# k26_baseboard_usb_c_conn.net
KiCad netlist of a schematic drawn in Altium Designer
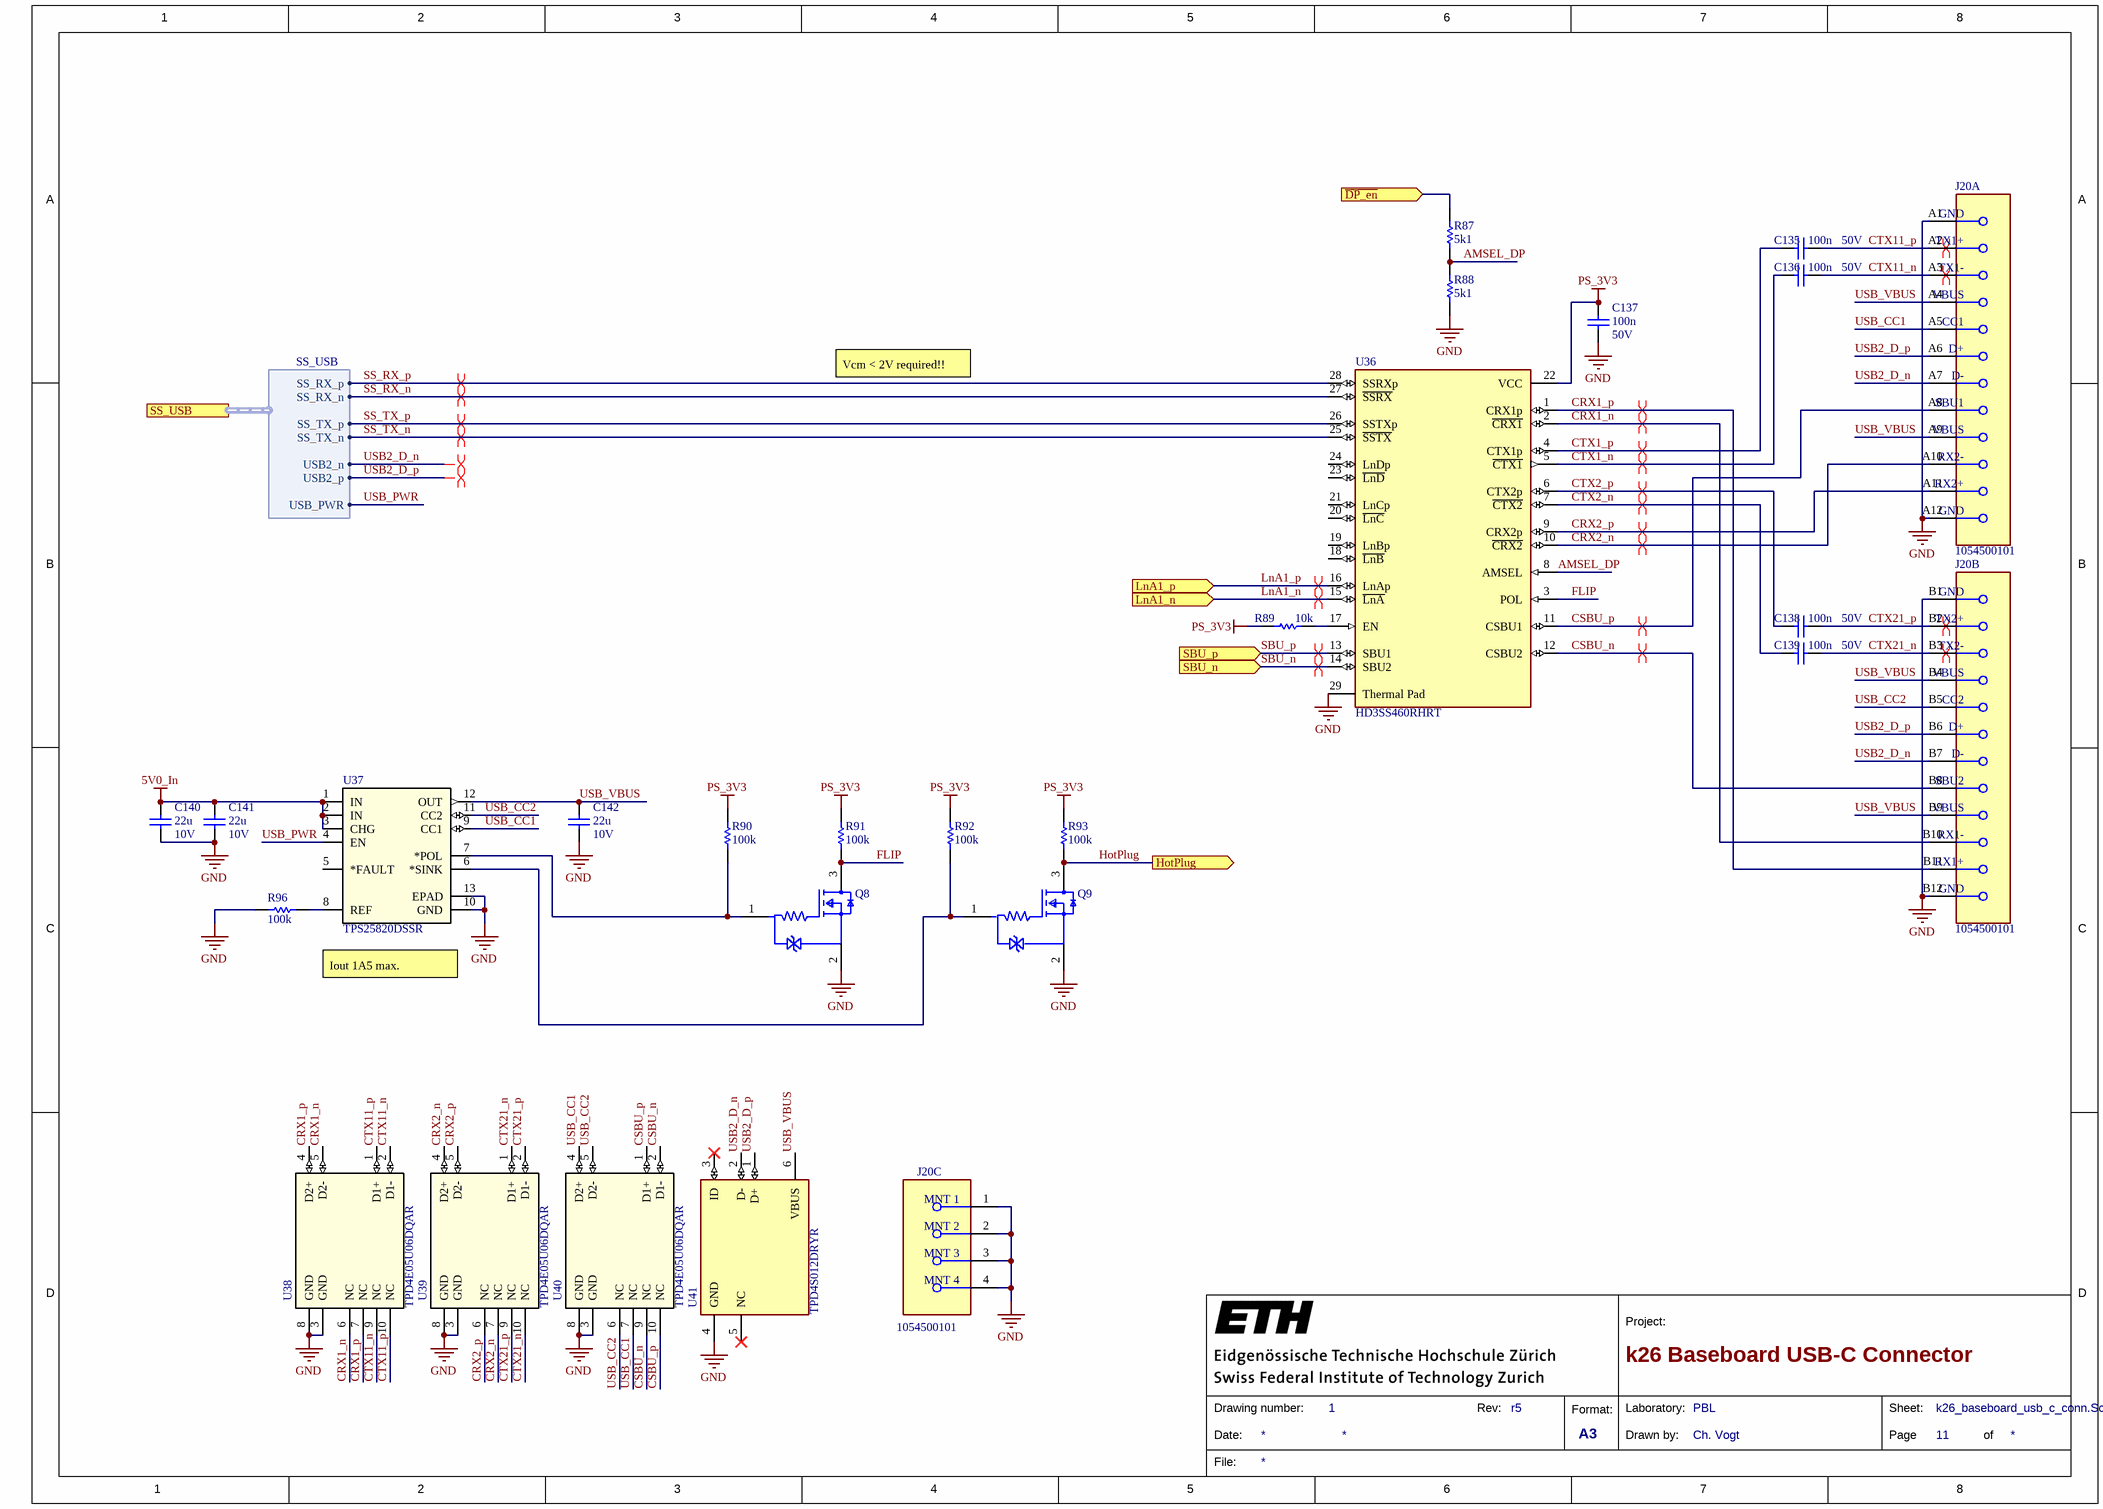
[diagram p0: k26_baseboard_usb_c_conn.SchDoc]

(export (version "E")
  (design (tool "Eeschema 10.0.6"))
  (components
    (comp (ref "C135")
      (value "100n")
      (footprint "k26_FPGA_drone_baseboard:CAPC0402")
      (fields
        (field (name "MANUFACTURER") "Yageo")
        (field (name "MANUFACTURER PART NUMBER") "CC0402KRX5R9BB104")
        (field (name "RATED DC VOLTAGE (URDC)") "50V")
      )
      (libsource (lib "k26_FPGA_drone_baseboard") (part "cap0402"))
    )
    (comp (ref "C136")
      (value "100n")
      (footprint "k26_FPGA_drone_baseboard:CAPC0402")
      (fields
        (field (name "MANUFACTURER") "Yageo")
        (field (name "MANUFACTURER PART NUMBER") "CC0402KRX5R9BB104")
        (field (name "RATED DC VOLTAGE (URDC)") "50V")
      )
      (libsource (lib "k26_FPGA_drone_baseboard") (part "cap0402"))
    )
    (comp (ref "C137")
      (value "100n")
      (footprint "k26_FPGA_drone_baseboard:CAPC0402")
      (fields
        (field (name "MANUFACTURER") "Yageo")
        (field (name "MANUFACTURER PART NUMBER") "CC0402KRX5R9BB104")
        (field (name "RATED DC VOLTAGE (URDC)") "50V")
      )
      (libsource (lib "k26_FPGA_drone_baseboard") (part "cap0402"))
    )
    (comp (ref "C138")
      (value "100n")
      (footprint "k26_FPGA_drone_baseboard:CAPC0402")
      (fields
        (field (name "MANUFACTURER") "Yageo")
        (field (name "MANUFACTURER PART NUMBER") "CC0402KRX5R9BB104")
        (field (name "RATED DC VOLTAGE (URDC)") "50V")
      )
      (libsource (lib "k26_FPGA_drone_baseboard") (part "cap0402"))
    )
    (comp (ref "C139")
      (value "100n")
      (footprint "k26_FPGA_drone_baseboard:CAPC0402")
      (fields
        (field (name "MANUFACTURER") "Yageo")
        (field (name "MANUFACTURER PART NUMBER") "CC0402KRX5R9BB104")
        (field (name "RATED DC VOLTAGE (URDC)") "50V")
      )
      (libsource (lib "k26_FPGA_drone_baseboard") (part "cap0402"))
    )
    (comp (ref "C140")
      (value "22u")
      (footprint "k26_FPGA_drone_baseboard:CAPC1206")
      (fields
        (field (name "MANUFACTURER") "Kyocera AVX")
        (field (name "MANUFACTURER PART NUMBER") "1206ZC226KAT2A")
        (field (name "RATED DC VOLTAGE (URDC)") "10V")
      )
      (libsource (lib "k26_FPGA_drone_baseboard") (part "cap1206"))
    )
    (comp (ref "C141")
      (value "22u")
      (footprint "k26_FPGA_drone_baseboard:CAPC1206")
      (fields
        (field (name "MANUFACTURER") "Kyocera AVX")
        (field (name "MANUFACTURER PART NUMBER") "1206ZC226KAT2A")
        (field (name "RATED DC VOLTAGE (URDC)") "10V")
      )
      (libsource (lib "k26_FPGA_drone_baseboard") (part "cap1206"))
    )
    (comp (ref "C142")
      (value "22u")
      (footprint "k26_FPGA_drone_baseboard:CAPC1206")
      (fields
        (field (name "MANUFACTURER") "Kyocera AVX")
        (field (name "MANUFACTURER PART NUMBER") "1206ZC226KAT2A")
        (field (name "RATED DC VOLTAGE (URDC)") "10V")
      )
      (libsource (lib "k26_FPGA_drone_baseboard") (part "cap1206"))
    )
    (comp (ref "J20")
      (value "1054500101")
      (footprint "k26_FPGA_drone_baseboard:FP-1054500101-MFG")
      (description "CONN RCP USB3.1 TYPEC 24P SMD RA")
      (fields
        (field (name "MANUFACTURER") "Molex")
        (field (name "OCTOPART") "https://octopart.com/105450-0101-molex-68082325")
      )
      (libsource (lib "") (part "CONN RCP USB3.1_1"))
    )
    (comp (ref "Q8")
      (value "RUM001L02T2CL")
      (footprint "FP-VMT3-MFG")
      (description "MOSFET N-CH 20V 0.1A VMT3")
      (fields
        (field (name "MANUFACTURER") "Rohm")
        (field (name "OCTOPART") "https://octopart.com/rum001l02t2cl-rohm-24403092")
      )
      (libsource (lib "k26_FPGA_drone_baseboard") (part "CMP-08982-000008-1"))
    )
    (comp (ref "Q9")
      (value "RUM001L02T2CL")
      (footprint "FP-VMT3-MFG")
      (description "MOSFET N-CH 20V 0.1A VMT3")
      (fields
        (field (name "MANUFACTURER") "Rohm")
        (field (name "OCTOPART") "https://octopart.com/rum001l02t2cl-rohm-24403092")
      )
      (libsource (lib "k26_FPGA_drone_baseboard") (part "CMP-08982-000008-1"))
    )
    (comp (ref "R87")
      (value "5k1")
      (footprint "k26_FPGA_drone_baseboard:RES0402")
      (fields
        (field (name "MANUFACTURER") "Yageo")
        (field (name "MANUFACTURER PART NUMBER") "RC0402FR-075K1L")
        (field (name "TOLERANCE") "1%")
      )
      (libsource (lib "k26_FPGA_drone_baseboard") (part "res0402"))
    )
    (comp (ref "R88")
      (value "5k1")
      (footprint "k26_FPGA_drone_baseboard:RES0402")
      (fields
        (field (name "MANUFACTURER") "Yageo")
        (field (name "MANUFACTURER PART NUMBER") "RC0402FR-075K1L")
        (field (name "TOLERANCE") "1%")
      )
      (libsource (lib "k26_FPGA_drone_baseboard") (part "res0402"))
    )
    (comp (ref "R89")
      (value "10k")
      (footprint "k26_FPGA_drone_baseboard:RES0402")
      (fields
        (field (name "MANUFACTURER") "Panasonic")
        (field (name "MANUFACTURER PART NUMBER") "ERJ-2RKF1002X")
        (field (name "TOLERANCE") "1%")
      )
      (libsource (lib "k26_FPGA_drone_baseboard") (part "res0402"))
    )
    (comp (ref "R90")
      (value "100k")
      (footprint "k26_FPGA_drone_baseboard:RES0402")
      (fields
        (field (name "MANUFACTURER") "Panasonic")
        (field (name "MANUFACTURER PART NUMBER") "ERJ-2RKF1003X")
        (field (name "TOLERANCE") "1%")
      )
      (libsource (lib "k26_FPGA_drone_baseboard") (part "res0402"))
    )
    (comp (ref "R91")
      (value "100k")
      (footprint "k26_FPGA_drone_baseboard:RES0402")
      (fields
        (field (name "MANUFACTURER") "Panasonic")
        (field (name "MANUFACTURER PART NUMBER") "ERJ-2RKF1003X")
        (field (name "TOLERANCE") "1%")
      )
      (libsource (lib "k26_FPGA_drone_baseboard") (part "res0402"))
    )
    (comp (ref "R92")
      (value "100k")
      (footprint "k26_FPGA_drone_baseboard:RES0402")
      (fields
        (field (name "MANUFACTURER") "Panasonic")
        (field (name "MANUFACTURER PART NUMBER") "ERJ-2RKF1003X")
        (field (name "TOLERANCE") "1%")
      )
      (libsource (lib "k26_FPGA_drone_baseboard") (part "res0402"))
    )
    (comp (ref "R93")
      (value "100k")
      (footprint "k26_FPGA_drone_baseboard:RES0402")
      (fields
        (field (name "MANUFACTURER") "Panasonic")
        (field (name "MANUFACTURER PART NUMBER") "ERJ-2RKF1003X")
        (field (name "TOLERANCE") "1%")
      )
      (libsource (lib "k26_FPGA_drone_baseboard") (part "res0402"))
    )
    (comp (ref "R96")
      (value "100k")
      (footprint "k26_FPGA_drone_baseboard:RES0402")
      (fields
        (field (name "MANUFACTURER") "Panasonic")
        (field (name "MANUFACTURER PART NUMBER") "ERJ-2RKF1003X")
        (field (name "TOLERANCE") "1%")
      )
      (libsource (lib "k26_FPGA_drone_baseboard") (part "res0402"))
    )
    (comp (ref "U36")
      (value "HD3SS460RHRT")
      (footprint "FP-RHR0028A-IPC_C")
      (description "IC MUX/DEMUX 4CH TYPE C2 28WQFN")
      (libsource (lib "k26_FPGA_drone_baseboard") (part "a69b51bd9502c85b4efb80e5a27bd8a"))
    )
    (comp (ref "U37")
      (value "TPS25820DSSR")
      (footprint "DSS12_P9X2_TEX")
      (description "No Description Available")
      (fields (field (name "COPYRIGHT") "Copyright (C) 2023 Ultra Librarian. All rights reserved."))
      (libsource (lib "k26_FPGA_drone_baseboard") (part "TPS25820DSSR"))
    )
    (comp (ref "U38")
      (value "TPD4E05U06DQAR")
      (footprint "DQA0010A")
      (description "No Description Available")
      (fields
        (field (name "MANUFACTURER") "Texas Instruments")
        (field (name "COPYRIGHT") "Copyright (C) 2022 Ultra Librarian. All rights reserved.")
      )
      (libsource (lib "k26_FPGA_drone_baseboard") (part "TPD4E05U06DQAR"))
    )
    (comp (ref "U39")
      (value "TPD4E05U06DQAR")
      (footprint "DQA0010A")
      (description "No Description Available")
      (fields
        (field (name "MANUFACTURER") "Texas Instruments")
        (field (name "COPYRIGHT") "Copyright (C) 2022 Ultra Librarian. All rights reserved.")
      )
      (libsource (lib "k26_FPGA_drone_baseboard") (part "TPD4E05U06DQAR"))
    )
    (comp (ref "U40")
      (value "TPD4E05U06DQAR")
      (footprint "DQA0010A")
      (description "No Description Available")
      (fields
        (field (name "MANUFACTURER") "Texas Instruments")
        (field (name "COPYRIGHT") "Copyright (C) 2022 Ultra Librarian. All rights reserved.")
      )
      (libsource (lib "k26_FPGA_drone_baseboard") (part "TPD4E05U06DQAR"))
    )
    (comp (ref "U41")
      (value "TPD4S012DRYR")
      (footprint "FP-DRY0006A-MFG")
      (description "TVS DIODE 5.5V 6SON")
      (fields (field (name "MANUFACTURER") "Texas Instruments"))
      (libsource (lib "k26_FPGA_drone_baseboard") (part "CMP-0326-00038-4"))
    )
  )
  (nets
    (net (code "2") (name "/AMSEL_DP") (class "Default")
      (node (ref "R87") (pin "1") (pinfunction "1_1") (pintype "passive"))
      (node (ref "R88") (pin "2") (pinfunction "2_2") (pintype "passive"))
      (node (ref "U36") (pin "8") (pinfunction "AMSEL_8") (pintype "input"))
    )
    (net (code "3") (name "/CRX1_n") (class "Default")
      (node (ref "J20") (pin "B10") (pinfunction "RX1-_B10") (pintype "passive"))
      (node (ref "U36") (pin "2") (pinfunction "~{CRX1}_2") (pintype "bidirectional"))
      (node (ref "U38") (pin "5") (pinfunction "D2-_5") (pintype "bidirectional"))
      (node (ref "U38") (pin "6") (pinfunction "NC_6") (pintype "passive"))
    )
    (net (code "4") (name "/CRX1_p") (class "Default")
      (node (ref "J20") (pin "B11") (pinfunction "RX1+_B11") (pintype "passive"))
      (node (ref "U36") (pin "1") (pinfunction "CRX1p_1") (pintype "bidirectional"))
      (node (ref "U38") (pin "4") (pinfunction "D2+_4") (pintype "bidirectional"))
      (node (ref "U38") (pin "7") (pinfunction "NC_7") (pintype "passive"))
    )
    (net (code "5") (name "/CRX2_n") (class "Default")
      (node (ref "J20") (pin "A10") (pinfunction "RX2-_A10") (pintype "passive"))
      (node (ref "U36") (pin "10") (pinfunction "~{CRX2}_10") (pintype "bidirectional"))
      (node (ref "U39") (pin "4") (pinfunction "D2+_4") (pintype "bidirectional"))
      (node (ref "U39") (pin "7") (pinfunction "NC_7") (pintype "passive"))
    )
    (net (code "6") (name "/CRX2_p") (class "Default")
      (node (ref "J20") (pin "A11") (pinfunction "RX2+_A11") (pintype "passive"))
      (node (ref "U36") (pin "9") (pinfunction "CRX2p_9") (pintype "bidirectional"))
      (node (ref "U39") (pin "5") (pinfunction "D2-_5") (pintype "bidirectional"))
      (node (ref "U39") (pin "6") (pinfunction "NC_6") (pintype "passive"))
    )
    (net (code "7") (name "/CSBU_n") (class "Default")
      (node (ref "J20") (pin "B8") (pinfunction "SBU2_B8") (pintype "passive"))
      (node (ref "U36") (pin "12") (pinfunction "CSBU2_12") (pintype "bidirectional"))
      (node (ref "U40") (pin "2") (pinfunction "D1-_2") (pintype "bidirectional"))
      (node (ref "U40") (pin "9") (pinfunction "NC_9") (pintype "passive"))
    )
    (net (code "8") (name "/CSBU_p") (class "Default")
      (node (ref "J20") (pin "A8") (pinfunction "SBU1_A8") (pintype "passive"))
      (node (ref "U36") (pin "11") (pinfunction "CSBU1_11") (pintype "bidirectional"))
      (node (ref "U40") (pin "1") (pinfunction "D1+_1") (pintype "bidirectional"))
      (node (ref "U40") (pin "10") (pinfunction "NC_10") (pintype "passive"))
    )
    (net (code "9") (name "/CTX1_n") (class "Default")
      (node (ref "C136") (pin "2") (pinfunction "2_2") (pintype "passive"))
      (node (ref "U36") (pin "5") (pinfunction "~{CTX1}_5") (pintype "output"))
    )
    (net (code "10") (name "/CTX1_p") (class "Default")
      (node (ref "C135") (pin "2") (pinfunction "2_2") (pintype "passive"))
      (node (ref "U36") (pin "4") (pinfunction "CTX1p_4") (pintype "bidirectional"))
    )
    (net (code "11") (name "/CTX2_n") (class "Default")
      (node (ref "C139") (pin "2") (pinfunction "2_2") (pintype "passive"))
      (node (ref "U36") (pin "7") (pinfunction "~{CTX2}_7") (pintype "bidirectional"))
    )
    (net (code "12") (name "/CTX2_p") (class "Default")
      (node (ref "C138") (pin "2") (pinfunction "2_2") (pintype "passive"))
      (node (ref "U36") (pin "6") (pinfunction "CTX2p_6") (pintype "bidirectional"))
    )
    (net (code "13") (name "/CTX11_n") (class "Default")
      (node (ref "C136") (pin "1") (pinfunction "1_1") (pintype "passive"))
      (node (ref "J20") (pin "A3") (pinfunction "TX1-_A3") (pintype "passive"))
      (node (ref "U38") (pin "2") (pinfunction "D1-_2") (pintype "bidirectional"))
      (node (ref "U38") (pin "9") (pinfunction "NC_9") (pintype "passive"))
    )
    (net (code "14") (name "/CTX11_p") (class "Default")
      (node (ref "C135") (pin "1") (pinfunction "1_1") (pintype "passive"))
      (node (ref "J20") (pin "A2") (pinfunction "TX1+_A2") (pintype "passive"))
      (node (ref "U38") (pin "1") (pinfunction "D1+_1") (pintype "bidirectional"))
      (node (ref "U38") (pin "10") (pinfunction "NC_10") (pintype "passive"))
    )
    (net (code "15") (name "/CTX21_n") (class "Default")
      (node (ref "C139") (pin "1") (pinfunction "1_1") (pintype "passive"))
      (node (ref "J20") (pin "B3") (pinfunction "TX2-_B3") (pintype "passive"))
      (node (ref "U39") (pin "1") (pinfunction "D1+_1") (pintype "bidirectional"))
      (node (ref "U39") (pin "10") (pinfunction "NC_10") (pintype "passive"))
    )
    (net (code "16") (name "/CTX21_p") (class "Default")
      (node (ref "C138") (pin "1") (pinfunction "1_1") (pintype "passive"))
      (node (ref "J20") (pin "B2") (pinfunction "TX2+_B2") (pintype "passive"))
      (node (ref "U39") (pin "2") (pinfunction "D1-_2") (pintype "bidirectional"))
      (node (ref "U39") (pin "9") (pinfunction "NC_9") (pintype "passive"))
    )
    (net (code "17") (name "/FLIP") (class "Default")
      (node (ref "Q8") (pin "3") (pinfunction "Drain_3") (pintype "passive"))
      (node (ref "R91") (pin "1") (pinfunction "1_1") (pintype "passive"))
      (node (ref "U36") (pin "3") (pinfunction "POL_3") (pintype "input"))
    )
    (net (code "18") (name "/HotPlug") (class "Default")
      (node (ref "Q9") (pin "3") (pinfunction "Drain_3") (pintype "passive"))
      (node (ref "R93") (pin "1") (pinfunction "1_1") (pintype "passive"))
    )
    (net (code "19") (name "/LnA1_n") (class "Default")
      (node (ref "U36") (pin "15") (pinfunction "~{LnA}_15") (pintype "bidirectional"))
    )
    (net (code "20") (name "/LnA1_p") (class "Default")
      (node (ref "U36") (pin "16") (pinfunction "LnAp_16") (pintype "bidirectional"))
    )
    (net (code "21") (name "/SBU_n") (class "Default")
      (node (ref "U36") (pin "14") (pinfunction "SBU2_14") (pintype "bidirectional"))
    )
    (net (code "22") (name "/SBU_p") (class "Default")
      (node (ref "U36") (pin "13") (pinfunction "SBU1_13") (pintype "bidirectional"))
    )
    (net (code "23") (name "/SS_RX_n") (class "Default")
      (node (ref "U36") (pin "27") (pinfunction "~{SSRX}_27") (pintype "bidirectional"))
    )
    (net (code "24") (name "/SS_RX_p") (class "Default")
      (node (ref "U36") (pin "28") (pinfunction "SSRXp_28") (pintype "bidirectional"))
    )
    (net (code "25") (name "/SS_TX_n") (class "Default")
      (node (ref "U36") (pin "25") (pinfunction "~{SSTX}_25") (pintype "bidirectional"))
    )
    (net (code "26") (name "/SS_TX_p") (class "Default")
      (node (ref "U36") (pin "26") (pinfunction "SSTXp_26") (pintype "bidirectional"))
    )
    (net (code "27") (name "/USB2_D_n") (class "Default")
      (node (ref "J20") (pin "A7") (pinfunction "D-_A7") (pintype "passive"))
      (node (ref "J20") (pin "B7") (pinfunction "D-_B7") (pintype "passive"))
      (node (ref "U41") (pin "2") (pinfunction "D-_2") (pintype "bidirectional"))
    )
    (net (code "28") (name "/USB2_D_p") (class "Default")
      (node (ref "J20") (pin "A6") (pinfunction "D+_A6") (pintype "passive"))
      (node (ref "J20") (pin "B6") (pinfunction "D+_B6") (pintype "passive"))
      (node (ref "U41") (pin "1") (pinfunction "D+_1") (pintype "bidirectional"))
    )
    (net (code "29") (name "/USB_CC1") (class "Default")
      (node (ref "J20") (pin "A5") (pinfunction "CC1_A5") (pintype "passive"))
      (node (ref "U37") (pin "9") (pinfunction "CC1_9") (pintype "bidirectional"))
      (node (ref "U40") (pin "4") (pinfunction "D2+_4") (pintype "bidirectional"))
      (node (ref "U40") (pin "7") (pinfunction "NC_7") (pintype "passive"))
    )
    (net (code "30") (name "/USB_CC2") (class "Default")
      (node (ref "J20") (pin "B5") (pinfunction "CC2_B5") (pintype "passive"))
      (node (ref "U37") (pin "11") (pinfunction "CC2_11") (pintype "bidirectional"))
      (node (ref "U40") (pin "5") (pinfunction "D2-_5") (pintype "bidirectional"))
      (node (ref "U40") (pin "6") (pinfunction "NC_6") (pintype "passive"))
    )
    (net (code "31") (name "/USB_PWR") (class "Default")
      (node (ref "U37") (pin "4") (pinfunction "EN_4") (pintype "passive"))
    )
    (net (code "32") (name "/USB_VBUS") (class "Default")
      (node (ref "C142") (pin "2") (pinfunction "2_2") (pintype "passive"))
      (node (ref "J20") (pin "A4") (pinfunction "VBUS_A4") (pintype "passive"))
      (node (ref "J20") (pin "A9") (pinfunction "VBUS_A9") (pintype "passive"))
      (node (ref "J20") (pin "B4") (pinfunction "VBUS_B4") (pintype "passive"))
      (node (ref "J20") (pin "B9") (pinfunction "VBUS_B9") (pintype "passive"))
      (node (ref "U37") (pin "12") (pinfunction "OUT_12") (pintype "output"))
      (node (ref "U41") (pin "6") (pinfunction "VBUS_6") (pintype "passive"))
    )
    (net (code "34") (name "/~{DP_en}") (class "Default")
      (node (ref "R87") (pin "2") (pinfunction "2_2") (pintype "passive"))
    )
    (net (code "35") (name "5V0_In") (class "Default")
      (node (ref "C140") (pin "2") (pinfunction "2_2") (pintype "passive"))
      (node (ref "C141") (pin "2") (pinfunction "2_2") (pintype "passive"))
      (node (ref "U37") (pin "1") (pinfunction "IN_1") (pintype "passive"))
      (node (ref "U37") (pin "2") (pinfunction "IN_2") (pintype "passive"))
      (node (ref "U37") (pin "3") (pinfunction "CHG_3") (pintype "passive"))
    )
    (net (code "36") (name "GND") (class "Default")
      (node (ref "C137") (pin "2") (pinfunction "2_2") (pintype "passive"))
      (node (ref "C140") (pin "1") (pinfunction "1_1") (pintype "passive"))
      (node (ref "C141") (pin "1") (pinfunction "1_1") (pintype "passive"))
      (node (ref "C142") (pin "1") (pinfunction "1_1") (pintype "passive"))
      (node (ref "J20") (pin "1") (pinfunction "MNT_1_1") (pintype "passive"))
      (node (ref "J20") (pin "2") (pinfunction "MNT_2_2") (pintype "passive"))
      (node (ref "J20") (pin "3") (pinfunction "MNT_3_3") (pintype "passive"))
      (node (ref "J20") (pin "4") (pinfunction "MNT_4_4") (pintype "passive"))
      (node (ref "J20") (pin "A1") (pinfunction "GND_A1") (pintype "passive"))
      (node (ref "J20") (pin "A12") (pinfunction "GND_A12") (pintype "passive"))
      (node (ref "J20") (pin "B1") (pinfunction "GND_B1") (pintype "passive"))
      (node (ref "J20") (pin "B12") (pinfunction "GND_B12") (pintype "passive"))
      (node (ref "Q8") (pin "2") (pinfunction "Source_2") (pintype "passive"))
      (node (ref "Q9") (pin "2") (pinfunction "Source_2") (pintype "passive"))
      (node (ref "R88") (pin "1") (pinfunction "1_1") (pintype "passive"))
      (node (ref "R96") (pin "1") (pinfunction "1_1") (pintype "passive"))
      (node (ref "U36") (pin "29") (pinfunction "Thermal_Pad_29") (pintype "power_in"))
      (node (ref "U37") (pin "10") (pinfunction "GND_10") (pintype "passive"))
      (node (ref "U37") (pin "13") (pinfunction "EPAD_13") (pintype "passive"))
      (node (ref "U38") (pin "3") (pinfunction "GND_3") (pintype "power_in"))
      (node (ref "U38") (pin "8") (pinfunction "GND_8") (pintype "power_in"))
      (node (ref "U39") (pin "3") (pinfunction "GND_3") (pintype "power_in"))
      (node (ref "U39") (pin "8") (pinfunction "GND_8") (pintype "power_in"))
      (node (ref "U40") (pin "3") (pinfunction "GND_3") (pintype "power_in"))
      (node (ref "U40") (pin "8") (pinfunction "GND_8") (pintype "power_in"))
      (node (ref "U41") (pin "4") (pinfunction "GND_4") (pintype "power_in"))
    )
    (net (code "37") (name "Net-(Q8-Gate)") (class "Default")
      (node (ref "Q8") (pin "1") (pinfunction "Gate_1") (pintype "passive"))
      (node (ref "R90") (pin "1") (pinfunction "1_1") (pintype "passive"))
      (node (ref "U37") (pin "7") (pinfunction "*POL_7") (pintype "passive"))
    )
    (net (code "38") (name "Net-(Q9-Gate)") (class "Default")
      (node (ref "Q9") (pin "1") (pinfunction "Gate_1") (pintype "passive"))
      (node (ref "R92") (pin "1") (pinfunction "1_1") (pintype "passive"))
      (node (ref "U37") (pin "6") (pinfunction "*SINK_6") (pintype "passive"))
    )
    (net (code "39") (name "Net-(U36-EN)") (class "Default")
      (node (ref "R89") (pin "1") (pinfunction "1_1") (pintype "passive"))
      (node (ref "U36") (pin "17") (pinfunction "EN_17") (pintype "input"))
    )
    (net (code "40") (name "Net-(U37-REF)") (class "Default")
      (node (ref "R96") (pin "2") (pinfunction "2_2") (pintype "passive"))
      (node (ref "U37") (pin "8") (pinfunction "REF_8") (pintype "passive"))
    )
    (net (code "41") (name "PS_3V3") (class "Default")
      (node (ref "C137") (pin "1") (pinfunction "1_1") (pintype "passive"))
      (node (ref "R89") (pin "2") (pinfunction "2_2") (pintype "passive"))
      (node (ref "R90") (pin "2") (pinfunction "2_2") (pintype "passive"))
      (node (ref "R91") (pin "2") (pinfunction "2_2") (pintype "passive"))
      (node (ref "R92") (pin "2") (pinfunction "2_2") (pintype "passive"))
      (node (ref "R93") (pin "2") (pinfunction "2_2") (pintype "passive"))
      (node (ref "U36") (pin "22") (pinfunction "VCC_22") (pintype "power_in"))
    )
    (net (code "42") (name "unconnected-(U36-LnBp-Pad19)") (class "Default")
      (node (ref "U36") (pin "19") (pinfunction "LnBp_19") (pintype "bidirectional"))
    )
    (net (code "43") (name "unconnected-(U36-LnCp-Pad21)") (class "Default")
      (node (ref "U36") (pin "21") (pinfunction "LnCp_21") (pintype "bidirectional"))
    )
    (net (code "44") (name "unconnected-(U36-LnDp-Pad24)") (class "Default")
      (node (ref "U36") (pin "24") (pinfunction "LnDp_24") (pintype "bidirectional"))
    )
    (net (code "45") (name "unconnected-(U36-~{LnB}-Pad18)") (class "Default")
      (node (ref "U36") (pin "18") (pinfunction "~{LnB}_18") (pintype "bidirectional"))
    )
    (net (code "46") (name "unconnected-(U36-~{LnC}-Pad20)") (class "Default")
      (node (ref "U36") (pin "20") (pinfunction "~{LnC}_20") (pintype "bidirectional"))
    )
    (net (code "47") (name "unconnected-(U36-~{LnD}-Pad23)") (class "Default")
      (node (ref "U36") (pin "23") (pinfunction "~{LnD}_23") (pintype "bidirectional"))
    )
    (net (code "48") (name "unconnected-(U37-*FAULT-Pad5)") (class "Default")
      (node (ref "U37") (pin "5") (pinfunction "*FAULT_5") (pintype "passive"))
    )
    (net (code "49") (name "unconnected-(U41-ID-Pad3)") (class "Default")
      (node (ref "U41") (pin "3") (pinfunction "ID_3") (pintype "bidirectional+no_connect"))
    )
    (net (code "50") (name "unconnected-(U41-NC-Pad5)") (class "Default")
      (node (ref "U41") (pin "5") (pinfunction "NC_5") (pintype "passive+no_connect"))
    )
  )
)
